# GPIO.net
KiCad netlist of a schematic drawn in EAGLE
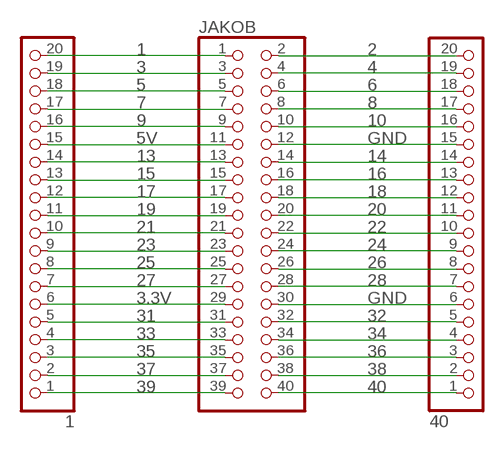
[diagram p0: schematic, sheet 1]

(export (version "E")
  (design (tool "Eeschema 10.0.6"))
  (components
    (comp (ref "1")
      (value "PINHD-1X20")
      (footprint "eagle-import:1X20")
      (libsource (lib "eagle-import") (part "PINHD-1X20"))
    )
    (comp (ref "40")
      (value "PINHD-1X20")
      (footprint "eagle-import:1X20")
      (libsource (lib "eagle-import") (part "PINHD-1X20"))
    )
    (comp (ref "JAKOB")
      (value "PINHD-2X20")
      (footprint "eagle-import:2X20")
      (libsource (lib "eagle-import") (part "PINHD-2X20"))
    )
  )
  (nets
    (net (code "1") (name "/1") (class "Default")
      (node (ref "1") (pin "20") (pinfunction "20_20") (pintype "passive"))
      (node (ref "JAKOB") (pin "1") (pinfunction "1_1") (pintype "passive"))
    )
    (net (code "2") (name "/2") (class "Default")
      (node (ref "40") (pin "20") (pinfunction "20_20") (pintype "passive"))
      (node (ref "JAKOB") (pin "2") (pinfunction "2_2") (pintype "passive"))
    )
    (net (code "3") (name "/3") (class "Default")
      (node (ref "1") (pin "19") (pinfunction "19_19") (pintype "passive"))
      (node (ref "JAKOB") (pin "3") (pinfunction "3_3") (pintype "passive"))
    )
    (net (code "4") (name "/3.3V") (class "Default")
      (node (ref "1") (pin "6") (pinfunction "6_6") (pintype "passive"))
      (node (ref "JAKOB") (pin "29") (pinfunction "29_29") (pintype "passive"))
    )
    (net (code "5") (name "/4") (class "Default")
      (node (ref "40") (pin "19") (pinfunction "19_19") (pintype "passive"))
      (node (ref "JAKOB") (pin "4") (pinfunction "4_4") (pintype "passive"))
    )
    (net (code "6") (name "/5") (class "Default")
      (node (ref "1") (pin "18") (pinfunction "18_18") (pintype "passive"))
      (node (ref "JAKOB") (pin "5") (pinfunction "5_5") (pintype "passive"))
    )
    (net (code "7") (name "/5V") (class "Default")
      (node (ref "1") (pin "15") (pinfunction "15_15") (pintype "passive"))
      (node (ref "JAKOB") (pin "11") (pinfunction "11_11") (pintype "passive"))
    )
    (net (code "8") (name "/6") (class "Default")
      (node (ref "40") (pin "18") (pinfunction "18_18") (pintype "passive"))
      (node (ref "JAKOB") (pin "6") (pinfunction "6_6") (pintype "passive"))
    )
    (net (code "9") (name "/7") (class "Default")
      (node (ref "1") (pin "17") (pinfunction "17_17") (pintype "passive"))
      (node (ref "JAKOB") (pin "7") (pinfunction "7_7") (pintype "passive"))
    )
    (net (code "10") (name "/8") (class "Default")
      (node (ref "40") (pin "17") (pinfunction "17_17") (pintype "passive"))
      (node (ref "JAKOB") (pin "8") (pinfunction "8_8") (pintype "passive"))
    )
    (net (code "11") (name "/9") (class "Default")
      (node (ref "1") (pin "16") (pinfunction "16_16") (pintype "passive"))
      (node (ref "JAKOB") (pin "9") (pinfunction "9_9") (pintype "passive"))
    )
    (net (code "12") (name "/10") (class "Default")
      (node (ref "40") (pin "16") (pinfunction "16_16") (pintype "passive"))
      (node (ref "JAKOB") (pin "10") (pinfunction "10_10") (pintype "passive"))
    )
    (net (code "13") (name "/13") (class "Default")
      (node (ref "1") (pin "14") (pinfunction "14_14") (pintype "passive"))
      (node (ref "JAKOB") (pin "13") (pinfunction "13_13") (pintype "passive"))
    )
    (net (code "14") (name "/14") (class "Default")
      (node (ref "40") (pin "14") (pinfunction "14_14") (pintype "passive"))
      (node (ref "JAKOB") (pin "14") (pinfunction "14_14") (pintype "passive"))
    )
    (net (code "15") (name "/15") (class "Default")
      (node (ref "1") (pin "13") (pinfunction "13_13") (pintype "passive"))
      (node (ref "JAKOB") (pin "15") (pinfunction "15_15") (pintype "passive"))
    )
    (net (code "16") (name "/16") (class "Default")
      (node (ref "40") (pin "13") (pinfunction "13_13") (pintype "passive"))
      (node (ref "JAKOB") (pin "16") (pinfunction "16_16") (pintype "passive"))
    )
    (net (code "17") (name "/17") (class "Default")
      (node (ref "1") (pin "12") (pinfunction "12_12") (pintype "passive"))
      (node (ref "JAKOB") (pin "17") (pinfunction "17_17") (pintype "passive"))
    )
    (net (code "18") (name "/18") (class "Default")
      (node (ref "40") (pin "12") (pinfunction "12_12") (pintype "passive"))
      (node (ref "JAKOB") (pin "18") (pinfunction "18_18") (pintype "passive"))
    )
    (net (code "19") (name "/19") (class "Default")
      (node (ref "1") (pin "11") (pinfunction "11_11") (pintype "passive"))
      (node (ref "JAKOB") (pin "19") (pinfunction "19_19") (pintype "passive"))
    )
    (net (code "20") (name "/20") (class "Default")
      (node (ref "40") (pin "11") (pinfunction "11_11") (pintype "passive"))
      (node (ref "JAKOB") (pin "20") (pinfunction "20_20") (pintype "passive"))
    )
    (net (code "21") (name "/21") (class "Default")
      (node (ref "1") (pin "10") (pinfunction "10_10") (pintype "passive"))
      (node (ref "JAKOB") (pin "21") (pinfunction "21_21") (pintype "passive"))
    )
    (net (code "22") (name "/22") (class "Default")
      (node (ref "40") (pin "10") (pinfunction "10_10") (pintype "passive"))
      (node (ref "JAKOB") (pin "22") (pinfunction "22_22") (pintype "passive"))
    )
    (net (code "23") (name "/23") (class "Default")
      (node (ref "1") (pin "9") (pinfunction "9_9") (pintype "passive"))
      (node (ref "JAKOB") (pin "23") (pinfunction "23_23") (pintype "passive"))
    )
    (net (code "24") (name "/24") (class "Default")
      (node (ref "40") (pin "9") (pinfunction "9_9") (pintype "passive"))
      (node (ref "JAKOB") (pin "24") (pinfunction "24_24") (pintype "passive"))
    )
    (net (code "25") (name "/25") (class "Default")
      (node (ref "1") (pin "8") (pinfunction "8_8") (pintype "passive"))
      (node (ref "JAKOB") (pin "25") (pinfunction "25_25") (pintype "passive"))
    )
    (net (code "26") (name "/26") (class "Default")
      (node (ref "40") (pin "8") (pinfunction "8_8") (pintype "passive"))
      (node (ref "JAKOB") (pin "26") (pinfunction "26_26") (pintype "passive"))
    )
    (net (code "27") (name "/27") (class "Default")
      (node (ref "1") (pin "7") (pinfunction "7_7") (pintype "passive"))
      (node (ref "JAKOB") (pin "27") (pinfunction "27_27") (pintype "passive"))
    )
    (net (code "28") (name "/28") (class "Default")
      (node (ref "40") (pin "7") (pinfunction "7_7") (pintype "passive"))
      (node (ref "JAKOB") (pin "28") (pinfunction "28_28") (pintype "passive"))
    )
    (net (code "29") (name "/31") (class "Default")
      (node (ref "1") (pin "5") (pinfunction "5_5") (pintype "passive"))
      (node (ref "JAKOB") (pin "31") (pinfunction "31_31") (pintype "passive"))
    )
    (net (code "30") (name "/32") (class "Default")
      (node (ref "40") (pin "5") (pinfunction "5_5") (pintype "passive"))
      (node (ref "JAKOB") (pin "32") (pinfunction "32_32") (pintype "passive"))
    )
    (net (code "31") (name "/33") (class "Default")
      (node (ref "1") (pin "4") (pinfunction "4_4") (pintype "passive"))
      (node (ref "JAKOB") (pin "33") (pinfunction "33_33") (pintype "passive"))
    )
    (net (code "32") (name "/34") (class "Default")
      (node (ref "40") (pin "4") (pinfunction "4_4") (pintype "passive"))
      (node (ref "JAKOB") (pin "34") (pinfunction "34_34") (pintype "passive"))
    )
    (net (code "33") (name "/35") (class "Default")
      (node (ref "1") (pin "3") (pinfunction "3_3") (pintype "passive"))
      (node (ref "JAKOB") (pin "35") (pinfunction "35_35") (pintype "passive"))
    )
    (net (code "34") (name "/36") (class "Default")
      (node (ref "40") (pin "3") (pinfunction "3_3") (pintype "passive"))
      (node (ref "JAKOB") (pin "36") (pinfunction "36_36") (pintype "passive"))
    )
    (net (code "35") (name "/37") (class "Default")
      (node (ref "1") (pin "2") (pinfunction "2_2") (pintype "passive"))
      (node (ref "JAKOB") (pin "37") (pinfunction "37_37") (pintype "passive"))
    )
    (net (code "36") (name "/38") (class "Default")
      (node (ref "40") (pin "2") (pinfunction "2_2") (pintype "passive"))
      (node (ref "JAKOB") (pin "38") (pinfunction "38_38") (pintype "passive"))
    )
    (net (code "37") (name "/39") (class "Default")
      (node (ref "1") (pin "1") (pinfunction "1_1") (pintype "passive"))
      (node (ref "JAKOB") (pin "39") (pinfunction "39_39") (pintype "passive"))
    )
    (net (code "38") (name "/40") (class "Default")
      (node (ref "40") (pin "1") (pinfunction "1_1") (pintype "passive"))
      (node (ref "JAKOB") (pin "40") (pinfunction "40_40") (pintype "passive"))
    )
    (net (code "39") (name "/GND") (class "Default")
      (node (ref "40") (pin "15") (pinfunction "15_15") (pintype "passive"))
      (node (ref "40") (pin "6") (pinfunction "6_6") (pintype "passive"))
      (node (ref "JAKOB") (pin "12") (pinfunction "12_12") (pintype "passive"))
      (node (ref "JAKOB") (pin "30") (pinfunction "30_30") (pintype "passive"))
    )
  )
)
